# BEP31_RPM_BAR_switchedRES_2.net
KiCad netlist of a schematic drawn in EAGLE
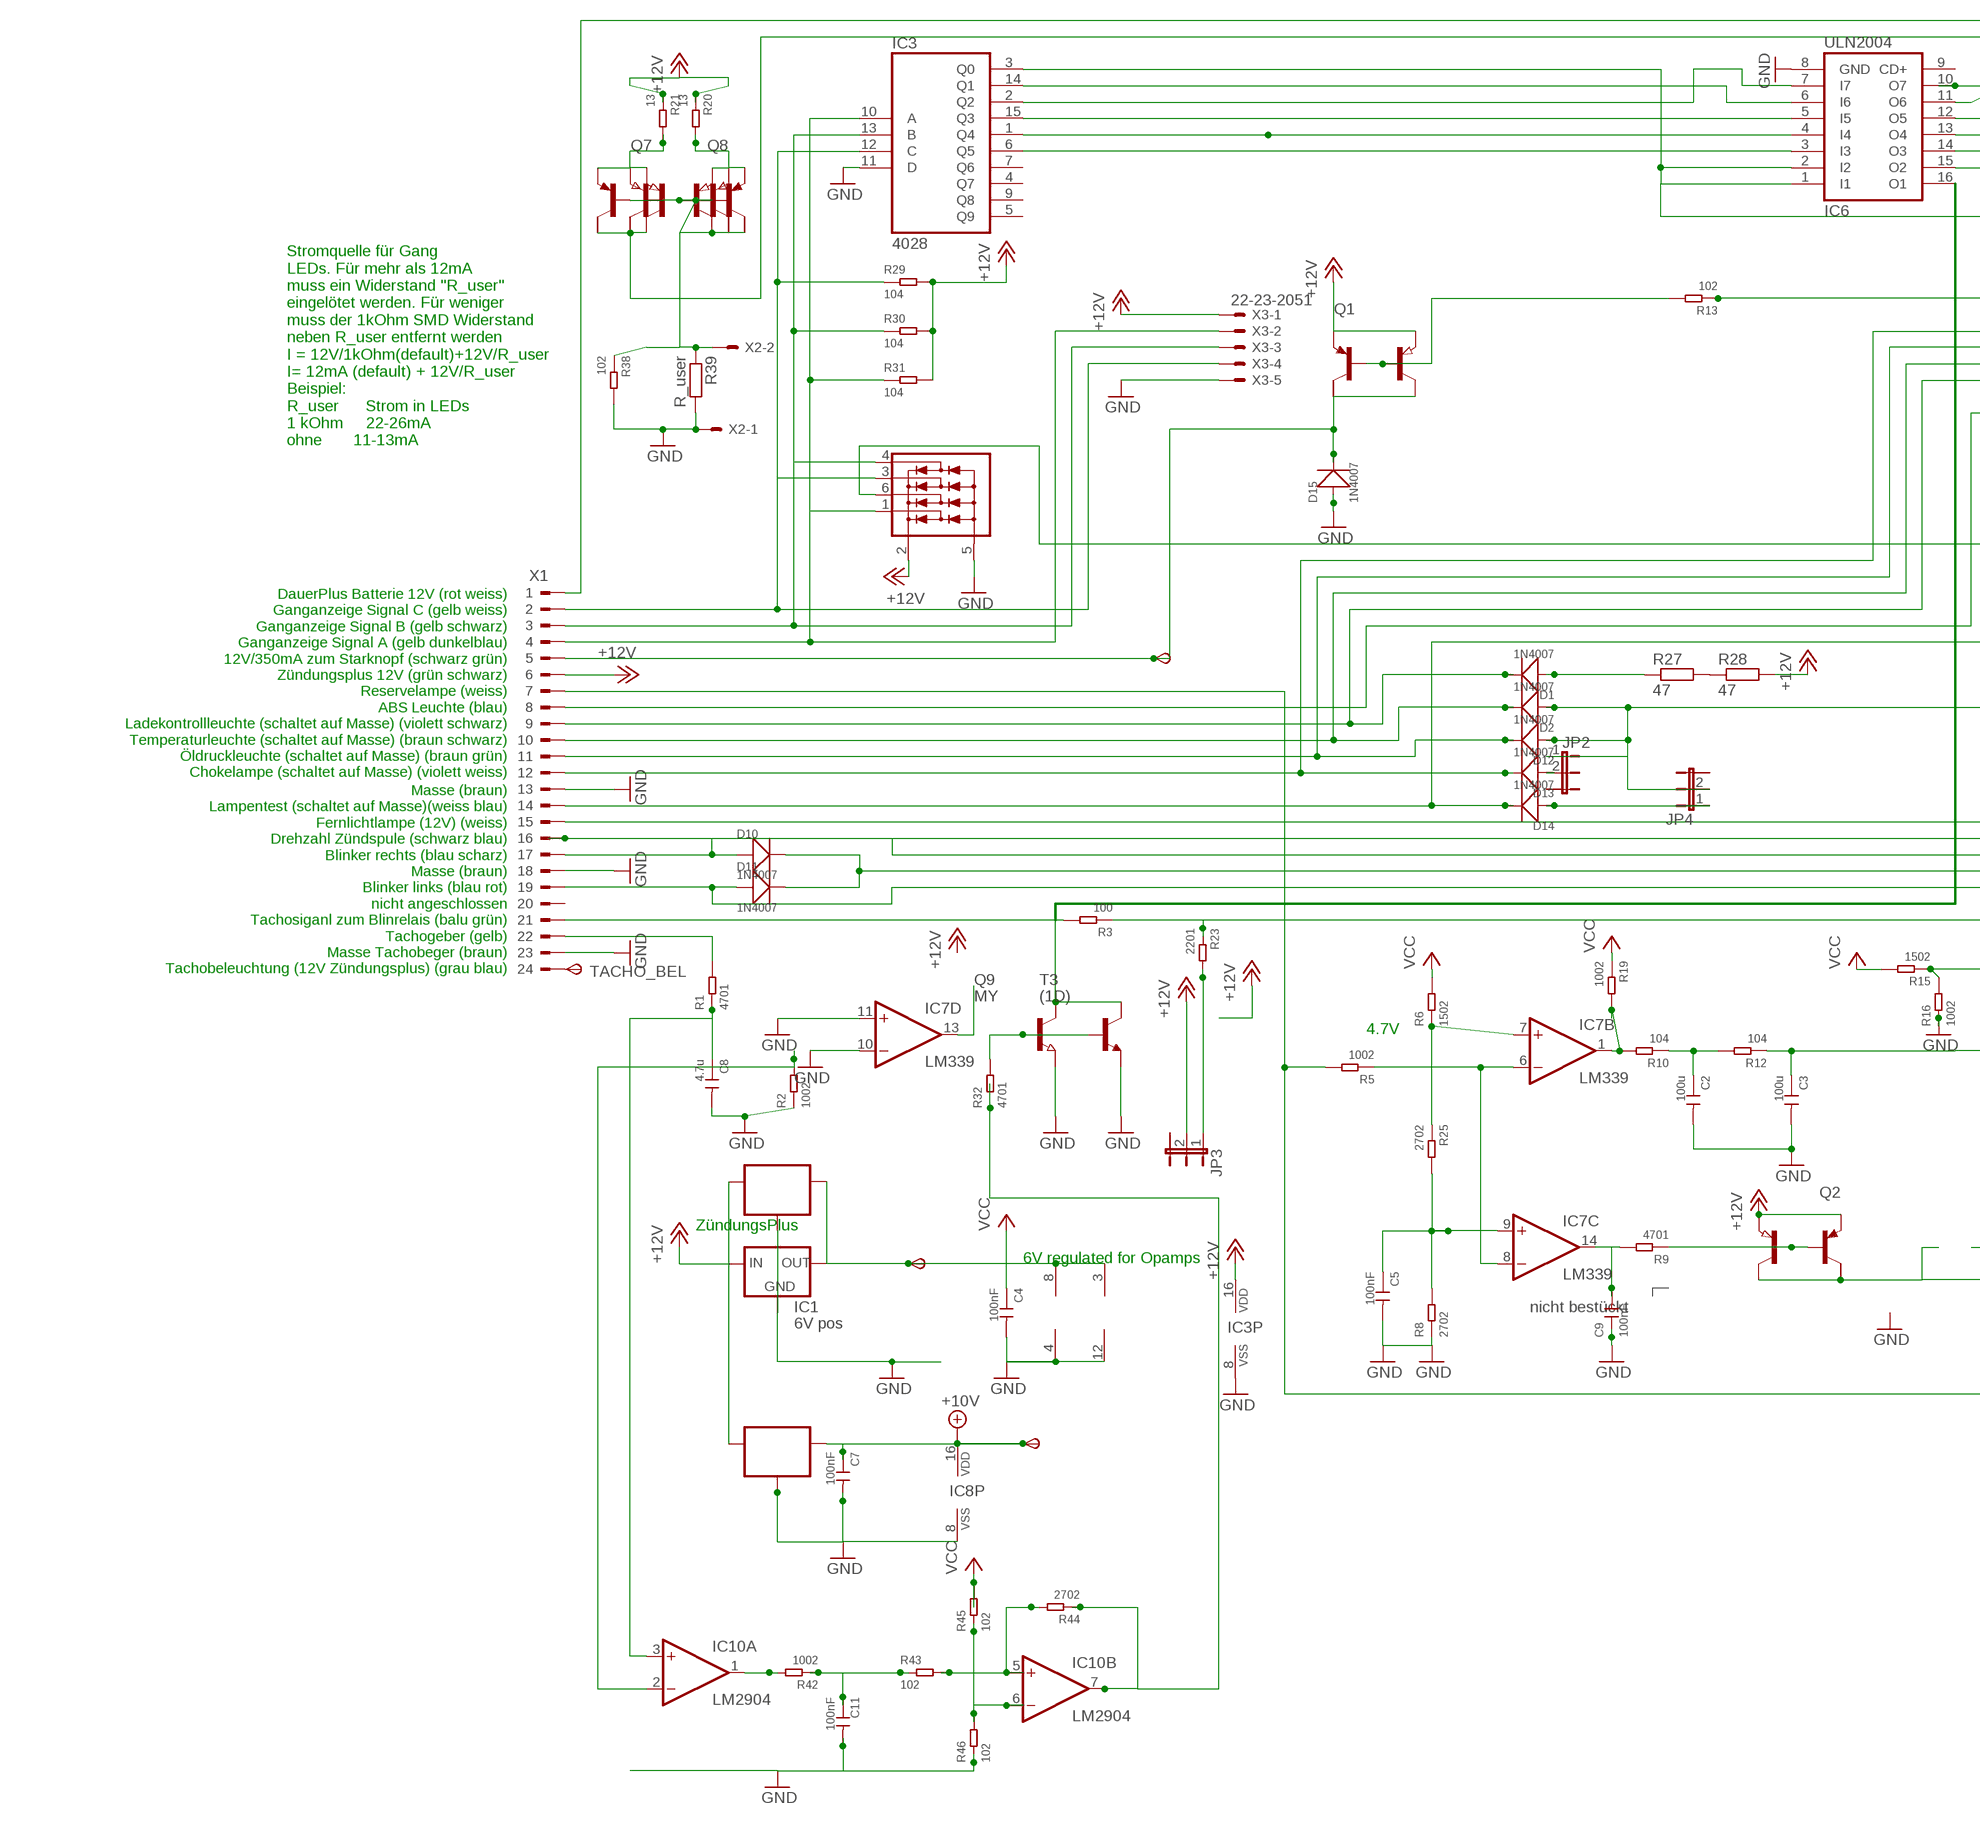
[diagram p0: schematic, sheet 1, part 1 of 2]
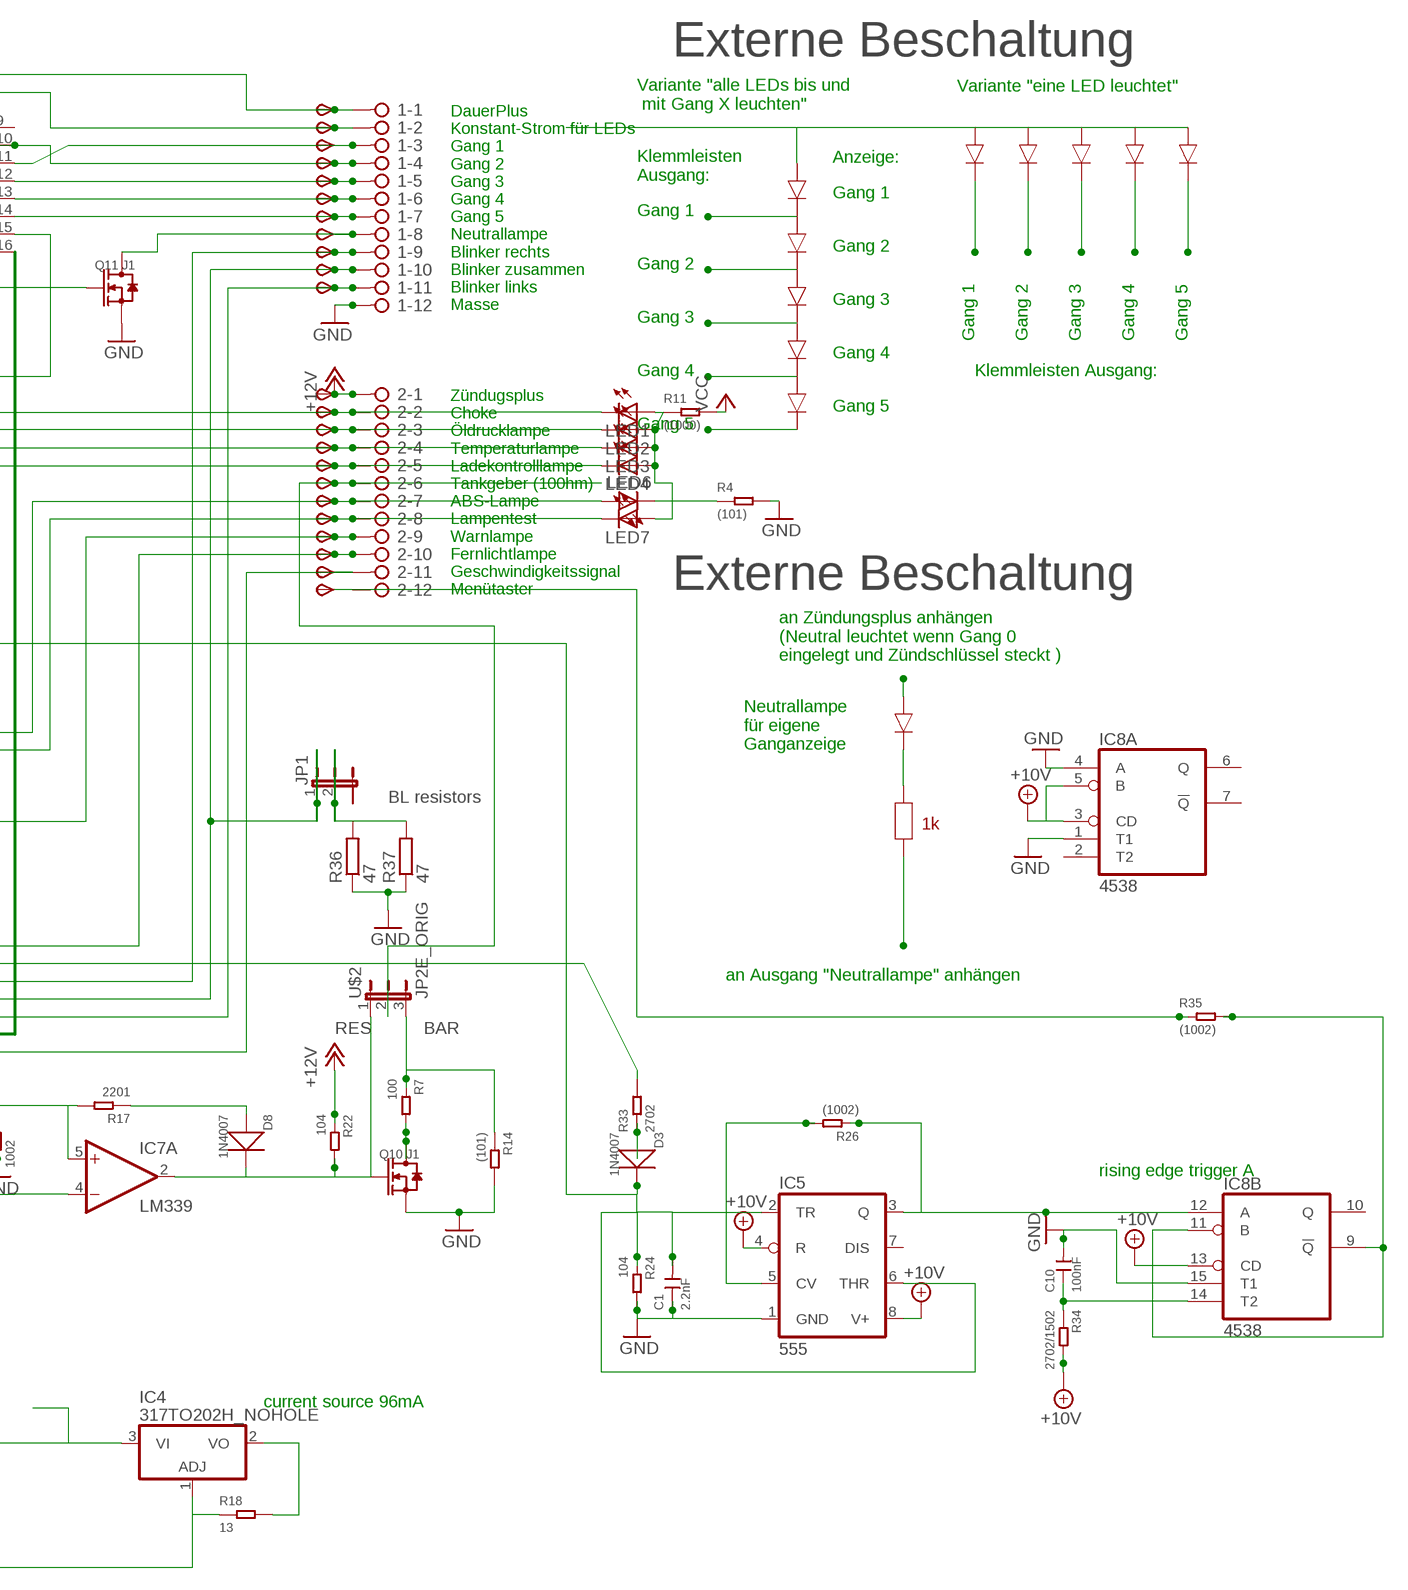
[diagram p1: schematic, sheet 1, part 2 of 2]

(export (version "E")
  (design (tool "Eeschema 10.0.6"))
  (components
    (comp (ref "1")
      (value "2081-1132")
      (footprint "eagle-import:12-PIN")
      (libsource (lib "eagle-import") (part "2081-1132"))
    )
    (comp (ref "2")
      (value "2081-1132")
      (footprint "eagle-import:12-PIN")
      (libsource (lib "eagle-import") (part "2081-1132"))
    )
    (comp (ref "6V")
      (value "TPSB2.0")
      (footprint "eagle-import:B2.0")
      (libsource (lib "eagle-import") (part "TPSB2.0"))
    )
    (comp (ref "10V")
      (value "TPSB2.0")
      (footprint "eagle-import:B2.0")
      (libsource (lib "eagle-import") (part "TPSB2.0"))
    )
    (comp (ref "C1")
      (value "2.2nF")
      (footprint "eagle-import:C0805")
      (fields (field (name "MPN") "CC0805KRX7R9BB104"))
      (libsource (lib "eagle-import") (part "CERAMIC-100NF-50V-10%-X7R(0805)"))
    )
    (comp (ref "C2")
      (value "100u")
      (footprint "eagle-import:C1206")
      (fields (field (name "MPN") "GRM31CR60J107ME39L"))
      (libsource (lib "eagle-import") (part "CERAMIC-100UF-6.3V-20%-X5R(1206)"))
    )
    (comp (ref "C3")
      (value "100u")
      (footprint "eagle-import:C1206")
      (fields (field (name "MPN") "GRM31CR60J107ME39L"))
      (libsource (lib "eagle-import") (part "CERAMIC-100UF-6.3V-20%-X5R(1206)"))
    )
    (comp (ref "C4")
      (value "100nF")
      (footprint "eagle-import:C0805")
      (fields (field (name "MPN") "CC0805KRX7R9BB104"))
      (libsource (lib "eagle-import") (part "CERAMIC-100NF-50V-10%-X7R(0805)"))
    )
    (comp (ref "C5")
      (value "100nF")
      (footprint "eagle-import:C0805")
      (fields (field (name "MPN") "CC0805KRX7R9BB104"))
      (libsource (lib "eagle-import") (part "CERAMIC-100NF-50V-10%-X7R(0805)"))
    )
    (comp (ref "C7")
      (value "100nF")
      (footprint "eagle-import:C0805")
      (fields (field (name "MPN") "CC0805KRX7R9BB104"))
      (libsource (lib "eagle-import") (part "CERAMIC-100NF-50V-10%-X7R(0805)"))
    )
    (comp (ref "C8")
      (value "4.7u")
      (footprint "eagle-import:C0805")
      (fields (field (name "MPN") "CC0805KKX5R8BB475"))
      (libsource (lib "eagle-import") (part "CERAMIC-4.7UF-25V-10%-X5R(0805)"))
    )
    (comp (ref "C9")
      (value "100nF")
      (footprint "eagle-import:C0805")
      (fields (field (name "MPN") "CC0805KRX7R9BB104"))
      (libsource (lib "eagle-import") (part "CERAMIC-100NF-50V-10%-X7R(0805)"))
    )
    (comp (ref "C10")
      (value "100nF")
      (footprint "eagle-import:C0805")
      (fields (field (name "MPN") "CC0805KRX7R9BB104"))
      (libsource (lib "eagle-import") (part "CERAMIC-100NF-50V-10%-X7R(0805)"))
    )
    (comp (ref "C11")
      (value "100nF")
      (footprint "eagle-import:C0805")
      (fields (field (name "MPN") "CC0805KRX7R9BB104"))
      (libsource (lib "eagle-import") (part "CERAMIC-100NF-50V-10%-X7R(0805)"))
    )
    (comp (ref "D1")
      (value "1N4007")
      (footprint "eagle-import:DO-214AC")
      (libsource (lib "eagle-import") (part "DIODE-GEN-PURPOSE-1KV-1A(DO-214AC)"))
    )
    (comp (ref "D2")
      (value "1N4007")
      (footprint "eagle-import:DO-214AC-1206MOUNT")
      (libsource (lib "eagle-import") (part "DIODE-GEN-PURPOSE-1KV-1A(DO-214AC)DO-214AC/1206"))
    )
    (comp (ref "D3")
      (value "1N4007")
      (footprint "eagle-import:DO-214AC")
      (libsource (lib "eagle-import") (part "DIODE-GEN-PURPOSE-1KV-1A(DO-214AC)"))
    )
    (comp (ref "D8")
      (value "1N4007")
      (footprint "eagle-import:DO-214AC")
      (libsource (lib "eagle-import") (part "DIODE-GEN-PURPOSE-1KV-1A(DO-214AC)"))
    )
    (comp (ref "D10")
      (value "1N4007")
      (footprint "eagle-import:DO-214AC")
      (libsource (lib "eagle-import") (part "DIODE-GEN-PURPOSE-1KV-1A(DO-214AC)"))
    )
    (comp (ref "D11")
      (value "1N4007")
      (footprint "eagle-import:DO-214AC")
      (libsource (lib "eagle-import") (part "DIODE-GEN-PURPOSE-1KV-1A(DO-214AC)"))
    )
    (comp (ref "D12")
      (value "1N4007")
      (footprint "eagle-import:DO-214AC-1206MOUNT")
      (libsource (lib "eagle-import") (part "DIODE-GEN-PURPOSE-1KV-1A(DO-214AC)DO-214AC/1206"))
    )
    (comp (ref "D13")
      (value "1N4007")
      (footprint "eagle-import:DO-214AC-1206MOUNT")
      (libsource (lib "eagle-import") (part "DIODE-GEN-PURPOSE-1KV-1A(DO-214AC)DO-214AC/1206"))
    )
    (comp (ref "D14")
      (value "1N4007")
      (footprint "eagle-import:DO-214AC-1206MOUNT")
      (libsource (lib "eagle-import") (part "DIODE-GEN-PURPOSE-1KV-1A(DO-214AC)DO-214AC/1206"))
    )
    (comp (ref "D15")
      (value "1N4007")
      (footprint "eagle-import:DO-214AC")
      (libsource (lib "eagle-import") (part "DIODE-GEN-PURPOSE-1KV-1A(DO-214AC)"))
    )
    (comp (ref "IC1")
      (value "6V pos")
      (footprint "eagle-import:78LXX")
      (libsource (lib "eagle-import") (part "v-reg_78LXX"))
    )
    (comp (ref "IC2")
      (value "78LXXSOT89_ROUND")
      (footprint "eagle-import:SOT89_ROUND")
      (libsource (lib "eagle-import") (part "78LXXSOT89_ROUND"))
    )
    (comp (ref "IC3")
      (value "4028")
      (footprint "eagle-import:SO16")
      (libsource (lib "eagle-import") (part "4028D"))
    )
    (comp (ref "IC4")
      (value "317TO202H_NOHOLE")
      (footprint "eagle-import:TO220H_NOHOLE")
      (libsource (lib "eagle-import") (part "317TO202H_NOHOLE"))
    )
    (comp (ref "IC5")
      (value "555")
      (footprint "eagle-import:SO08")
      (libsource (lib "eagle-import") (part "555DNE"))
    )
    (comp (ref "IC6")
      (value "ULN2004")
      (footprint "eagle-import:SO16")
      (libsource (lib "eagle-import") (part "ULN2004AD"))
    )
    (comp (ref "IC7")
      (value "LM339")
      (footprint "eagle-import:SO14")
      (libsource (lib "eagle-import") (part "LM339D"))
    )
    (comp (ref "IC8")
      (value "4538")
      (footprint "eagle-import:SO16")
      (libsource (lib "eagle-import") (part "4538D"))
    )
    (comp (ref "IC9")
      (value "78LXXSOT89_ROUND")
      (footprint "eagle-import:SOT89_ROUND")
      (libsource (lib "eagle-import") (part "78LXXSOT89_ROUND"))
    )
    (comp (ref "IC10")
      (value "LM2904")
      (footprint "eagle-import:SO08")
      (libsource (lib "eagle-import") (part "LM358D"))
    )
    (comp (ref "JP1")
      (value "JP2EJP2_SMALLPADS")
      (footprint "eagle-import:JP2_SMALLPADS")
      (libsource (lib "eagle-import") (part "JP2EJP2_SMALLPADS"))
    )
    (comp (ref "JP2")
      (value "JP2EJP2_SMALLPADS")
      (footprint "eagle-import:JP2_SMALLPADS")
      (libsource (lib "eagle-import") (part "JP2EJP2_SMALLPADS"))
    )
    (comp (ref "JP3")
      (value "JP2EJP2_SMALLPADS")
      (footprint "eagle-import:JP2_SMALLPADS")
      (libsource (lib "eagle-import") (part "JP2EJP2_SMALLPADS"))
    )
    (comp (ref "JP4")
      (value "JP2EJP2_SMALLPADS")
      (footprint "eagle-import:JP2_SMALLPADS")
      (libsource (lib "eagle-import") (part "JP2EJP2_SMALLPADS"))
    )
    (comp (ref "LED1")
      (value "LEDLD260")
      (footprint "eagle-import:LD260")
      (libsource (lib "eagle-import") (part "LEDLD260"))
    )
    (comp (ref "LED2")
      (value "LEDLD260")
      (footprint "eagle-import:LD260")
      (libsource (lib "eagle-import") (part "LEDLD260"))
    )
    (comp (ref "LED3")
      (value "LEDLD260")
      (footprint "eagle-import:LD260")
      (libsource (lib "eagle-import") (part "LEDLD260"))
    )
    (comp (ref "LED4")
      (value "LEDLD260")
      (footprint "eagle-import:LD260")
      (libsource (lib "eagle-import") (part "LEDLD260"))
    )
    (comp (ref "LED6")
      (value "LEDLD260")
      (footprint "eagle-import:LD260")
      (libsource (lib "eagle-import") (part "LEDLD260"))
    )
    (comp (ref "LED7")
      (value "LEDLD260")
      (footprint "eagle-import:LD260")
      (libsource (lib "eagle-import") (part "LEDLD260"))
    )
    (comp (ref "Q1")
      (value "PNP-TRANSISTOR_SOT89")
      (footprint "eagle-import:SOT89")
      (libsource (lib "eagle-import") (part "PNP-TRANSISTOR_SOT89"))
    )
    (comp (ref "Q2")
      (value "PNP-TRANSISTOR_SOT89")
      (footprint "eagle-import:SOT89")
      (libsource (lib "eagle-import") (part "PNP-TRANSISTOR_SOT89"))
    )
    (comp (ref "Q3")
      (value "AH-16")
      (footprint "eagle-import:SOT223")
      (libsource (lib "eagle-import") (part "BCP53T1"))
    )
    (comp (ref "Q4")
      (value "(AH-16)")
      (footprint "eagle-import:SOT223")
      (libsource (lib "eagle-import") (part "BCP53T1"))
    )
    (comp (ref "Q5")
      (value "(AH-16)")
      (footprint "eagle-import:SOT223")
      (libsource (lib "eagle-import") (part "BCP53T1"))
    )
    (comp (ref "Q6")
      (value "(AH-16)")
      (footprint "eagle-import:SOT223")
      (libsource (lib "eagle-import") (part "BCP53T1"))
    )
    (comp (ref "Q7")
      (value "PNP-TRANSISTOR_SOT89")
      (footprint "eagle-import:SOT89")
      (libsource (lib "eagle-import") (part "PNP-TRANSISTOR_SOT89"))
    )
    (comp (ref "Q8")
      (value "PNP-TRANSISTOR_SOT89")
      (footprint "eagle-import:SOT89")
      (libsource (lib "eagle-import") (part "PNP-TRANSISTOR_SOT89"))
    )
    (comp (ref "Q9")
      (value "MY")
      (footprint "eagle-import:SOT89")
      (libsource (lib "eagle-import") (part "NPN-TRANSISTOR_SOT89"))
    )
    (comp (ref "Q10")
      (value "J1")
      (footprint "eagle-import:SOT-23")
      (fields (field (name "MPN") "BSS138W-7-F"))
      (libsource (lib "eagle-import") (part "SMD-MOSFET-N-CH-50V-200MA-BSS138W-7-F(SOT-23)"))
    )
    (comp (ref "Q11")
      (value "J1")
      (footprint "eagle-import:SOT-23")
      (fields (field (name "MPN") "BSS138W-7-F"))
      (libsource (lib "eagle-import") (part "SMD-MOSFET-N-CH-50V-200MA-BSS138W-7-F(SOT-23)"))
    )
    (comp (ref "R1")
      (value "4701")
      (footprint "eagle-import:R0805")
      (fields (field (name "MPN") "RC0805JR-074K7L"))
      (libsource (lib "eagle-import") (part "SMD-RES-4.7K-5%-1/8W(0805)"))
    )
    (comp (ref "R2")
      (value "1002")
      (footprint "eagle-import:R0805")
      (fields (field (name "MPN") "RC0805FR-0710KL"))
      (libsource (lib "eagle-import") (part "SMD-RES-10K-1%-1/8W(0805)"))
    )
    (comp (ref "R3")
      (value "100")
      (footprint "eagle-import:R0805")
      (fields (field (name "MPN") "RC0805JR-07220RL"))
      (libsource (lib "eagle-import") (part "SMD-RES-220R-5%-1/8W(0805)"))
    )
    (comp (ref "R4")
      (value "(101)")
      (footprint "eagle-import:R0805")
      (fields (field (name "MPN") "RC0805JR-07100RL"))
      (libsource (lib "eagle-import") (part "SMD-RES-100R-5%-1/8W(0805)"))
    )
    (comp (ref "R5")
      (value "1002")
      (footprint "eagle-import:R0805")
      (fields (field (name "MPN") "RC0805FR-0710KL"))
      (libsource (lib "eagle-import") (part "SMD-RES-10K-1%-1/8W(0805)"))
    )
    (comp (ref "R6")
      (value "1502")
      (footprint "eagle-import:R0805")
      (fields (field (name "MPN") "RC0805FR-0710KL"))
      (libsource (lib "eagle-import") (part "SMD-RES-10K-1%-1/8W(0805)"))
    )
    (comp (ref "R7")
      (value "100")
      (footprint "eagle-import:R0805")
      (fields (field (name "MPN") "RC0805JR-072K2L"))
      (libsource (lib "eagle-import") (part "SMD-RES-2.2K-5%-1/8W(0805)"))
    )
    (comp (ref "R8")
      (value "2702")
      (footprint "eagle-import:R0805")
      (fields (field (name "MPN") "RC0805JR-074K7L"))
      (libsource (lib "eagle-import") (part "SMD-RES-4.7K-5%-1/8W(0805)"))
    )
    (comp (ref "R9")
      (value "4701")
      (footprint "eagle-import:R0805")
      (fields (field (name "MPN") "RC0805JR-074K7L"))
      (libsource (lib "eagle-import") (part "SMD-RES-4.7K-5%-1/8W(0805)"))
    )
    (comp (ref "R10")
      (value "104")
      (footprint "eagle-import:R0805")
      (fields (field (name "MPN") "RC0805FR-0710KL"))
      (libsource (lib "eagle-import") (part "SMD-RES-10K-1%-1/8W(0805)"))
    )
    (comp (ref "R11")
      (value "(1000)")
      (footprint "eagle-import:R0805")
      (fields (field (name "MPN") "RC0805JR-07100RL"))
      (libsource (lib "eagle-import") (part "SMD-RES-100R-5%-1/8W(0805)"))
    )
    (comp (ref "R12")
      (value "104")
      (footprint "eagle-import:R0805")
      (fields (field (name "MPN") "RC0805FR-0710KL"))
      (libsource (lib "eagle-import") (part "SMD-RES-10K-1%-1/8W(0805)"))
    )
    (comp (ref "R13")
      (value "102")
      (footprint "eagle-import:R0805")
      (fields (field (name "MPN") "RC0805JR-071KL"))
      (libsource (lib "eagle-import") (part "SMD-RES-1K-5%-1/8W(0805)"))
    )
    (comp (ref "R14")
      (value "(101)")
      (footprint "eagle-import:R0805")
      (fields (field (name "MPN") "RC0805JR-072K2L"))
      (libsource (lib "eagle-import") (part "SMD-RES-2.2K-5%-1/8W(0805)"))
    )
    (comp (ref "R15")
      (value "1502")
      (footprint "eagle-import:R0805")
      (fields (field (name "MPN") "RC0805FR-0710KL"))
      (libsource (lib "eagle-import") (part "SMD-RES-10K-1%-1/8W(0805)"))
    )
    (comp (ref "R16")
      (value "1002")
      (footprint "eagle-import:R0805")
      (fields (field (name "MPN") "RC0805FR-0710KL"))
      (libsource (lib "eagle-import") (part "SMD-RES-10K-1%-1/8W(0805)"))
    )
    (comp (ref "R17")
      (value "2201")
      (footprint "eagle-import:R0805")
      (fields (field (name "MPN") "RC0805JR-072K2L"))
      (libsource (lib "eagle-import") (part "SMD-RES-2.2K-5%-1/8W(0805)"))
    )
    (comp (ref "R18")
      (value "13")
      (footprint "eagle-import:R1206")
      (fields (field (name "MPN") "RC1206JR-0713RL"))
      (libsource (lib "eagle-import") (part "SMD-RES-13R-5%-1/4W(1206)"))
    )
    (comp (ref "R19")
      (value "1002")
      (footprint "eagle-import:R0805")
      (fields (field (name "MPN") "RC0805FR-0710KL"))
      (libsource (lib "eagle-import") (part "SMD-RES-10K-1%-1/8W(0805)"))
    )
    (comp (ref "R20")
      (value "13")
      (footprint "eagle-import:R1206")
      (fields (field (name "MPN") "RC1206JR-0713RL"))
      (libsource (lib "eagle-import") (part "SMD-RES-13R-5%-1/4W(1206)"))
    )
    (comp (ref "R21")
      (value "13")
      (footprint "eagle-import:R1206")
      (fields (field (name "MPN") "RC1206JR-0713RL"))
      (libsource (lib "eagle-import") (part "SMD-RES-13R-5%-1/4W(1206)"))
    )
    (comp (ref "R22")
      (value "104")
      (footprint "eagle-import:R0805")
      (fields (field (name "MPN") "RC0805FR-0710KL"))
      (libsource (lib "eagle-import") (part "SMD-RES-10K-1%-1/8W(0805)"))
    )
    (comp (ref "R23")
      (value "2201")
      (footprint "eagle-import:R0805")
      (fields (field (name "MPN") "RC0805JR-072K2L"))
      (libsource (lib "eagle-import") (part "SMD-RES-2.2K-5%-1/8W(0805)"))
    )
    (comp (ref "R24")
      (value "104")
      (footprint "eagle-import:R0805")
      (fields (field (name "MPN") "RC0805FR-0710KL"))
      (libsource (lib "eagle-import") (part "SMD-RES-10K-1%-1/8W(0805)"))
    )
    (comp (ref "R25")
      (value "2702")
      (footprint "eagle-import:R0805")
      (fields (field (name "MPN") "RC0805JR-074K7L"))
      (libsource (lib "eagle-import") (part "SMD-RES-4.7K-5%-1/8W(0805)"))
    )
    (comp (ref "R26")
      (value "(1002)")
      (footprint "eagle-import:R0805")
      (fields (field (name "MPN") "RC0805FR-0710KL"))
      (libsource (lib "eagle-import") (part "SMD-RES-10K-1%-1/8W(0805)"))
    )
    (comp (ref "R27")
      (value "47")
      (footprint "eagle-import:V235_17_1MM")
      (libsource (lib "eagle-import") (part "R-EU_V235/17_1MM"))
    )
    (comp (ref "R28")
      (value "47")
      (footprint "eagle-import:V235_17_1MM")
      (libsource (lib "eagle-import") (part "R-EU_V235/17_1MM"))
    )
    (comp (ref "R29")
      (value "104")
      (footprint "eagle-import:R0805")
      (fields (field (name "MPN") "RC0805FR-0710KL"))
      (libsource (lib "eagle-import") (part "SMD-RES-10K-1%-1/8W(0805)"))
    )
    (comp (ref "R30")
      (value "104")
      (footprint "eagle-import:R0805")
      (fields (field (name "MPN") "RC0805FR-0710KL"))
      (libsource (lib "eagle-import") (part "SMD-RES-10K-1%-1/8W(0805)"))
    )
    (comp (ref "R31")
      (value "104")
      (footprint "eagle-import:R0805")
      (fields (field (name "MPN") "RC0805FR-0710KL"))
      (libsource (lib "eagle-import") (part "SMD-RES-10K-1%-1/8W(0805)"))
    )
    (comp (ref "R32")
      (value "4701")
      (footprint "eagle-import:R0805")
      (fields (field (name "MPN") "RC0805JR-074K7L"))
      (libsource (lib "eagle-import") (part "SMD-RES-4.7K-5%-1/8W(0805)"))
    )
    (comp (ref "R33")
      (value "2702")
      (footprint "eagle-import:R0805")
      (fields (field (name "MPN") "RC0805FR-0710KL"))
      (libsource (lib "eagle-import") (part "SMD-RES-10K-1%-1/8W(0805)"))
    )
    (comp (ref "R34")
      (value "2702/1502")
      (footprint "eagle-import:R0805")
      (fields (field (name "MPN") "RC0805JR-074K7L"))
      (libsource (lib "eagle-import") (part "SMD-RES-4.7K-5%-1/8W(0805)"))
    )
    (comp (ref "R35")
      (value "(1002)")
      (footprint "eagle-import:R0805")
      (fields (field (name "MPN") "RC0805JR-074K7L"))
      (libsource (lib "eagle-import") (part "SMD-RES-4.7K-5%-1/8W(0805)"))
    )
    (comp (ref "R36")
      (value "47")
      (footprint "eagle-import:V235_17_1MM")
      (libsource (lib "eagle-import") (part "R-EU_V235/17_1MM"))
    )
    (comp (ref "R37")
      (value "47")
      (footprint "eagle-import:V235_17_1MM")
      (libsource (lib "eagle-import") (part "R-EU_V235/17_1MM"))
    )
    (comp (ref "R38")
      (value "102")
      (footprint "eagle-import:R0805")
      (fields (field (name "MPN") "RC0805JR-071KL"))
      (libsource (lib "eagle-import") (part "SMD-RES-1K-5%-1/8W(0805)"))
    )
    (comp (ref "R39")
      (value "R_user")
      (footprint "eagle-import:R0805")
      (libsource (lib "eagle-import") (part "R-EU_R0805"))
    )
    (comp (ref "R42")
      (value "1002")
      (footprint "eagle-import:R0805")
      (fields (field (name "MPN") "RC0805FR-0710KL"))
      (libsource (lib "eagle-import") (part "SMD-RES-10K-1%-1/8W(0805)"))
    )
    (comp (ref "R43")
      (value "102")
      (footprint "eagle-import:R0805")
      (fields (field (name "MPN") "RC0805JR-071KL"))
      (libsource (lib "eagle-import") (part "SMD-RES-1K-5%-1/8W(0805)"))
    )
    (comp (ref "R44")
      (value "2702")
      (footprint "eagle-import:R0805")
      (fields (field (name "MPN") "RC0805JR-074K7L"))
      (libsource (lib "eagle-import") (part "SMD-RES-4.7K-5%-1/8W(0805)"))
    )
    (comp (ref "R45")
      (value "102")
      (footprint "eagle-import:R0805")
      (fields (field (name "MPN") "RC0805JR-071KL"))
      (libsource (lib "eagle-import") (part "SMD-RES-1K-5%-1/8W(0805)"))
    )
    (comp (ref "R46")
      (value "102")
      (footprint "eagle-import:R0805")
      (fields (field (name "MPN") "RC0805JR-071KL"))
      (libsource (lib "eagle-import") (part "SMD-RES-1K-5%-1/8W(0805)"))
    )
    (comp (ref "START")
      (value "TPSB2.0")
      (footprint "eagle-import:B2.0")
      (libsource (lib "eagle-import") (part "TPSB2.0"))
    )
    (comp (ref "T1")
      (value "PNP2SM8")
      (footprint "eagle-import:SM8")
      (libsource (lib "eagle-import") (part "PNP2SM8"))
    )
    (comp (ref "T3")
      (value "(1D)")
      (footprint "eagle-import:SOT23-BEC")
      (libsource (lib "eagle-import") (part "-NPN-SOT23-BECMMBTA42LT1"))
    )
    (comp (ref "TACHO_BEL")
      (value "TPSP1_1MM")
      (footprint "eagle-import:P1_1.0MM")
      (libsource (lib "eagle-import") (part "TPSP1_1MM"))
    )
    (comp (ref "TP1")
      (value "TPSB2.0")
      (footprint "eagle-import:B2.0")
      (libsource (lib "eagle-import") (part "TPSB2.0"))
    )
    (comp (ref "TP2")
      (value "TPSB2.0")
      (footprint "eagle-import:B2.0")
      (libsource (lib "eagle-import") (part "TPSB2.0"))
    )
    (comp (ref "TP3")
      (value "TPSB2.0")
      (footprint "eagle-import:B2.0")
      (libsource (lib "eagle-import") (part "TPSB2.0"))
    )
    (comp (ref "TP4")
      (value "TPSB2.0")
      (footprint "eagle-import:B2.0")
      (libsource (lib "eagle-import") (part "TPSB2.0"))
    )
    (comp (ref "TP5")
      (value "TPSB2.0")
      (footprint "eagle-import:B2.0")
      (libsource (lib "eagle-import") (part "TPSB2.0"))
    )
    (comp (ref "TP6")
      (value "TPSB2.0")
      (footprint "eagle-import:B2.0")
      (libsource (lib "eagle-import") (part "TPSB2.0"))
    )
    (comp (ref "TP7")
      (value "TPSB2.0")
      (footprint "eagle-import:B2.0")
      (libsource (lib "eagle-import") (part "TPSB2.0"))
    )
    (comp (ref "TP8")
      (value "TPSB2.0")
      (footprint "eagle-import:B2.0")
      (libsource (lib "eagle-import") (part "TPSB2.0"))
    )
    (comp (ref "TP9")
      (value "TPSB2.0")
      (footprint "eagle-import:B2.0")
      (libsource (lib "eagle-import") (part "TPSB2.0"))
    )
    (comp (ref "TP10")
      (value "TPSB2.0")
      (footprint "eagle-import:B2.0")
      (libsource (lib "eagle-import") (part "TPSB2.0"))
    )
    (comp (ref "TP11")
      (value "TPSB2.0")
      (footprint "eagle-import:B2.0")
      (libsource (lib "eagle-import") (part "TPSB2.0"))
    )
    (comp (ref "TP12")
      (value "TPSB2.0")
      (footprint "eagle-import:B2.0")
      (libsource (lib "eagle-import") (part "TPSB2.0"))
    )
    (comp (ref "TP13")
      (value "TPSB2.0")
      (footprint "eagle-import:B2.0")
      (libsource (lib "eagle-import") (part "TPSB2.0"))
    )
    (comp (ref "TP16")
      (value "TPSB2.0")
      (footprint "eagle-import:B2.0")
      (libsource (lib "eagle-import") (part "TPSB2.0"))
    )
    (comp (ref "TP17")
      (value "TPSB2.0")
      (footprint "eagle-import:B2.0")
      (libsource (lib "eagle-import") (part "TPSB2.0"))
    )
    (comp (ref "TP18")
      (value "TPSB2.0")
      (footprint "eagle-import:B2.0")
      (libsource (lib "eagle-import") (part "TPSB2.0"))
    )
    (comp (ref "TP19")
      (value "TPSB2.0")
      (footprint "eagle-import:B2.0")
      (libsource (lib "eagle-import") (part "TPSB2.0"))
    )
    (comp (ref "TP21")
      (value "TPSB2.0")
      (footprint "eagle-import:B2.0")
      (libsource (lib "eagle-import") (part "TPSB2.0"))
    )
    (comp (ref "TP22")
      (value "TPSB2.0")
      (footprint "eagle-import:B2.0")
      (libsource (lib "eagle-import") (part "TPSB2.0"))
    )
    (comp (ref "TP23")
      (value "TPSB2.0")
      (footprint "eagle-import:B2.0")
      (libsource (lib "eagle-import") (part "TPSB2.0"))
    )
    (comp (ref "TP24")
      (value "TPSB1,27")
      (footprint "eagle-import:B1,27")
      (libsource (lib "eagle-import") (part "TPSB1,27"))
    )
    (comp (ref "TP25")
      (value "TPSB2.0")
      (footprint "eagle-import:B2.0")
      (libsource (lib "eagle-import") (part "TPSB2.0"))
    )
    (comp (ref "TP26")
      (value "TPSB2.0")
      (footprint "eagle-import:B2.0")
      (libsource (lib "eagle-import") (part "TPSB2.0"))
    )
    (comp (ref "U$2")
      (value "JP2E_ORIG")
      (footprint "eagle-import:JP2_ORIG_SMALLPADS")
      (libsource (lib "eagle-import") (part "JP2E_ORIG"))
    )
    (comp (ref "U$3")
      (value "NUP4304SOT457_R")
      (footprint "eagle-import:SOT457R_PHILIPS")
      (libsource (lib "eagle-import") (part "NUP4304SOT457_R"))
    )
    (comp (ref "X1")
      (value "CON_BMWV2")
      (footprint "eagle-import:24-PIN_V2")
      (libsource (lib "eagle-import") (part "CON_BMWV2"))
    )
    (comp (ref "X2")
      (value "22-23-2021")
      (footprint "eagle-import:22-23-2021")
      (fields (field (name "MF") "MOLEX"))
      (libsource (lib "eagle-import") (part "22-23-2021"))
    )
    (comp (ref "X3")
      (value "22-23-2051")
      (footprint "eagle-import:22-23-2051")
      (fields (field (name "MF") "MOLEX"))
      (libsource (lib "eagle-import") (part "22-23-2051"))
    )
  )
  (nets
    (net (code "1") (name "+10V") (class "Default")
      (node (ref "10V") (pin "TP") (pinfunction "PP_TP") (pintype "input"))
      (node (ref "C7") (pin "1") (pinfunction "1_1") (pintype "passive"))
      (node (ref "IC5") (pin "4") (pinfunction "R_4") (pintype "input"))
      (node (ref "IC5") (pin "8") (pinfunction "V+_8") (pintype "power_in"))
      (node (ref "IC8") (pin "13") (pinfunction "CD_13") (pintype "input"))
      (node (ref "IC8") (pin "16") (pinfunction "VDD_16") (pintype "power_in"))
      (node (ref "IC8") (pin "3") (pinfunction "CD_3") (pintype "input"))
      (node (ref "IC8") (pin "5") (pinfunction "B_5") (pintype "input"))
      (node (ref "IC9") (pin "1") (pinfunction "OUT_1") (pintype "passive"))
      (node (ref "R34") (pin "2") (pinfunction "2_2") (pintype "passive"))
    )
    (net (code "2") (name "+12V") (class "Default")
      (node (ref "2") (pin "1") (pinfunction "KL_1") (pintype "passive"))
      (node (ref "IC1") (pin "IN") (pinfunction "IN_IN") (pintype "input"))
      (node (ref "IC2") (pin "3") (pinfunction "IN_3") (pintype "input"))
      (node (ref "IC3") (pin "16") (pinfunction "VDD_16") (pintype "power_in"))
      (node (ref "IC9") (pin "3") (pinfunction "IN_3") (pintype "input"))
      (node (ref "JP3") (pin "2") (pinfunction "2_2") (pintype "passive"))
      (node (ref "Q1") (pin "3") (pinfunction "E_3") (pintype "passive"))
      (node (ref "Q2") (pin "3") (pinfunction "E_3") (pintype "passive"))
      (node (ref "Q3") (pin "3") (pinfunction "E_3") (pintype "passive"))
      (node (ref "Q4") (pin "3") (pinfunction "E_3") (pintype "passive"))
      (node (ref "R20") (pin "1") (pinfunction "1_1") (pintype "passive"))
      (node (ref "R21") (pin "1") (pinfunction "1_1") (pintype "passive"))
      (node (ref "R22") (pin "1") (pinfunction "1_1") (pintype "passive"))
      (node (ref "R28") (pin "2") (pinfunction "2_2") (pintype "passive"))
      (node (ref "R29") (pin "2") (pinfunction "2_2") (pintype "passive"))
      (node (ref "R30") (pin "2") (pinfunction "2_2") (pintype "passive"))
      (node (ref "R31") (pin "2") (pinfunction "2_2") (pintype "passive"))
      (node (ref "TP12") (pin "TP") (pinfunction "PP_TP") (pintype "input"))
      (node (ref "U$3") (pin "2") (pinfunction "V+_2") (pintype "passive"))
      (node (ref "X1") (pin "6") (pinfunction "6_6") (pintype "passive"))
      (node (ref "X3") (pin "1") (pinfunction "S_1") (pintype "passive"))
    )
    (net (code "3") (name "GND") (class "Default")
      (node (ref "1") (pin "12") (pinfunction "KL_12") (pintype "passive"))
      (node (ref "C1") (pin "1") (pinfunction "1_1") (pintype "passive"))
      (node (ref "C10") (pin "2") (pinfunction "2_2") (pintype "passive"))
      (node (ref "C11") (pin "2") (pinfunction "2_2") (pintype "passive"))
      (node (ref "C2") (pin "2") (pinfunction "2_2") (pintype "passive"))
      (node (ref "C3") (pin "2") (pinfunction "2_2") (pintype "passive"))
      (node (ref "C4") (pin "2") (pinfunction "2_2") (pintype "passive"))
      (node (ref "C5") (pin "2") (pinfunction "2_2") (pintype "passive"))
      (node (ref "C7") (pin "2") (pinfunction "2_2") (pintype "passive"))
      (node (ref "C8") (pin "2") (pinfunction "2_2") (pintype "passive"))
      (node (ref "C9") (pin "1") (pinfunction "1_1") (pintype "passive"))
      (node (ref "D15") (pin "1") (pinfunction "+_1") (pintype "passive"))
      (node (ref "IC1") (pin "GND") (pinfunction "GND_GND") (pintype "input"))
      (node (ref "IC10") (pin "4") (pinfunction "V-_4") (pintype "power_in"))
      (node (ref "IC2") (pin "2") (pinfunction "GND_2") (pintype "input"))
      (node (ref "IC2") (pin "2@1") (pinfunction "GND_2@1") (pintype "input"))
      (node (ref "IC3") (pin "11") (pinfunction "D_11") (pintype "input"))
      (node (ref "IC3") (pin "8") (pinfunction "VSS_8") (pintype "power_in"))
      (node (ref "IC5") (pin "1") (pinfunction "GND_1") (pintype "power_in"))
      (node (ref "IC6") (pin "8") (pinfunction "GND_8") (pintype "power_in"))
      (node (ref "IC7") (pin "10") (pinfunction "-IN_10") (pintype "input"))
      (node (ref "IC7") (pin "11") (pinfunction "+IN_11") (pintype "input"))
      (node (ref "IC7") (pin "12") (pinfunction "GND_12") (pintype "power_in"))
      (node (ref "IC8") (pin "1") (pinfunction "T1_1") (pintype "input"))
      (node (ref "IC8") (pin "15") (pinfunction "T1_15") (pintype "input"))
      (node (ref "IC8") (pin "4") (pinfunction "A_4") (pintype "input"))
      (node (ref "IC8") (pin "8") (pinfunction "VSS_8") (pintype "power_in"))
      (node (ref "IC9") (pin "2") (pinfunction "GND_2") (pintype "input"))
      (node (ref "IC9") (pin "2@1") (pinfunction "GND_2@1") (pintype "input"))
      (node (ref "Q10") (pin "2") (pinfunction "S_2") (pintype "passive"))
      (node (ref "Q11") (pin "2") (pinfunction "S_2") (pintype "passive"))
      (node (ref "Q9") (pin "3") (pinfunction "E_3") (pintype "passive"))
      (node (ref "R14") (pin "2") (pinfunction "2_2") (pintype "passive"))
      (node (ref "R16") (pin "1") (pinfunction "1_1") (pintype "passive"))
      (node (ref "R2") (pin "1") (pinfunction "1_1") (pintype "passive"))
      (node (ref "R24") (pin "2") (pinfunction "2_2") (pintype "passive"))
      (node (ref "R36") (pin "1") (pinfunction "1_1") (pintype "passive"))
      (node (ref "R37") (pin "1") (pinfunction "1_1") (pintype "passive"))
      (node (ref "R38") (pin "2") (pinfunction "2_2") (pintype "passive"))
      (node (ref "R39") (pin "2") (pinfunction "2_2") (pintype "passive"))
      (node (ref "R4") (pin "2") (pinfunction "2_2") (pintype "passive"))
      (node (ref "R46") (pin "1") (pinfunction "1_1") (pintype "passive"))
      (node (ref "R8") (pin "1") (pinfunction "1_1") (pintype "passive"))
      (node (ref "T3") (pin "E") (pinfunction "E_E") (pintype "passive"))
      (node (ref "U$3") (pin "5") (pinfunction "V-_5") (pintype "passive"))
      (node (ref "X1") (pin "13") (pinfunction "13_13") (pintype "passive"))
      (node (ref "X1") (pin "18") (pinfunction "18_18") (pintype "passive"))
      (node (ref "X1") (pin "23") (pinfunction "23_23") (pintype "passive"))
      (node (ref "X2") (pin "1") (pinfunction "S_1") (pintype "passive"))
      (node (ref "X3") (pin "5") (pinfunction "S_5") (pintype "passive"))
    )
    (net (code "4") (name "Net-(1A-KL)") (class "Default")
      (node (ref "1") (pin "1") (pinfunction "KL_1") (pintype "passive"))
      (node (ref "TP1") (pin "TP") (pinfunction "PP_TP") (pintype "input"))
      (node (ref "X1") (pin "1") (pinfunction "1_1") (pintype "passive"))
    )
    (net (code "5") (name "Net-(1B-KL)") (class "Default")
      (node (ref "1") (pin "10") (pinfunction "KL_10") (pintype "passive"))
      (node (ref "D10") (pin "2") (pinfunction "-_2") (pintype "passive"))
      (node (ref "D11") (pin "2") (pinfunction "-_2") (pintype "passive"))
      (node (ref "JP1") (pin "1") (pinfunction "1_1") (pintype "passive"))
      (node (ref "TP10") (pin "TP") (pinfunction "PP_TP") (pintype "input"))
    )
    (net (code "6") (name "Net-(1C-KL)") (class "Default")
      (node (ref "1") (pin "11") (pinfunction "KL_11") (pintype "passive"))
      (node (ref "D11") (pin "1") (pinfunction "+_1") (pintype "passive"))
      (node (ref "TP11") (pin "TP") (pinfunction "PP_TP") (pintype "input"))
      (node (ref "X1") (pin "19") (pinfunction "19_19") (pintype "passive"))
    )
    (net (code "7") (name "Net-(1E-KL)") (class "Default")
      (node (ref "1") (pin "2") (pinfunction "KL_2") (pintype "passive"))
      (node (ref "Q5") (pin "2") (pinfunction "C_2") (pintype "passive"))
      (node (ref "Q8") (pin "2") (pinfunction "C_2") (pintype "passive"))
      (node (ref "T1") (pin "8") (pinfunction "C1_8") (pintype "passive"))
      (node (ref "TP2") (pin "TP") (pinfunction "PP_TP") (pintype "input"))
    )
    (net (code "8") (name "Net-(1F-KL)") (class "Default")
      (node (ref "1") (pin "3") (pinfunction "KL_3") (pintype "passive"))
      (node (ref "IC6") (pin "11") (pinfunction "O6_11") (pintype "open_collector"))
      (node (ref "TP3") (pin "TP") (pinfunction "PP_TP") (pintype "input"))
    )
    (net (code "9") (name "Net-(1G-KL)") (class "Default")
      (node (ref "1") (pin "4") (pinfunction "KL_4") (pintype "passive"))
      (node (ref "IC6") (pin "10") (pinfunction "O7_10") (pintype "open_collector"))
      (node (ref "TP4") (pin "TP") (pinfunction "PP_TP") (pintype "input"))
    )
    (net (code "10") (name "Net-(1H-KL)") (class "Default")
      (node (ref "1") (pin "5") (pinfunction "KL_5") (pintype "passive"))
      (node (ref "IC6") (pin "12") (pinfunction "O5_12") (pintype "open_collector"))
      (node (ref "TP5") (pin "TP") (pinfunction "PP_TP") (pintype "input"))
    )
    (net (code "11") (name "Net-(1I-KL)") (class "Default")
      (node (ref "1") (pin "6") (pinfunction "KL_6") (pintype "passive"))
      (node (ref "IC6") (pin "13") (pinfunction "O4_13") (pintype "open_collector"))
      (node (ref "TP6") (pin "TP") (pinfunction "PP_TP") (pintype "input"))
    )
    (net (code "12") (name "Net-(1J-KL)") (class "Default")
      (node (ref "1") (pin "7") (pinfunction "KL_7") (pintype "passive"))
      (node (ref "IC6") (pin "14") (pinfunction "O3_14") (pintype "open_collector"))
      (node (ref "TP7") (pin "TP") (pinfunction "PP_TP") (pintype "input"))
    )
    (net (code "13") (name "Net-(1K-KL)") (class "Default")
      (node (ref "1") (pin "8") (pinfunction "KL_8") (pintype "passive"))
      (node (ref "Q11") (pin "3") (pinfunction "D_3") (pintype "passive"))
      (node (ref "TP8") (pin "TP") (pinfunction "PP_TP") (pintype "input"))
    )
    (net (code "14") (name "Net-(1L-KL)") (class "Default")
      (node (ref "1") (pin "9") (pinfunction "KL_9") (pintype "passive"))
      (node (ref "D10") (pin "1") (pinfunction "+_1") (pintype "passive"))
      (node (ref "TP9") (pin "TP") (pinfunction "PP_TP") (pintype "input"))
      (node (ref "X1") (pin "17") (pinfunction "17_17") (pintype "passive"))
    )
    (net (code "15") (name "Net-(2B-KL)") (class "Default")
      (node (ref "2") (pin "10") (pinfunction "KL_10") (pintype "passive"))
      (node (ref "TP25") (pin "TP") (pinfunction "PP_TP") (pintype "input"))
      (node (ref "X1") (pin "15") (pinfunction "15_15") (pintype "passive"))
    )
    (net (code "16") (name "Net-(2C-KL)") (class "Default")
      (node (ref "2") (pin "11") (pinfunction "KL_11") (pintype "passive"))
      (node (ref "R23") (pin "1") (pinfunction "1_1") (pintype "passive"))
      (node (ref "R3") (pin "1") (pinfunction "1_1") (pintype "passive"))
      (node (ref "TP26") (pin "TP") (pinfunction "PP_TP") (pintype "input"))
    )
    (net (code "17") (name "Net-(2D-KL)") (class "Default")
      (node (ref "2") (pin "12") (pinfunction "KL_12") (pintype "passive"))
      (node (ref "R35") (pin "1") (pinfunction "1_1") (pintype "passive"))
      (node (ref "TP13") (pin "TP") (pinfunction "PP_TP") (pintype "input"))
    )
    (net (code "18") (name "Net-(2E-KL)") (class "Default")
      (node (ref "2") (pin "2") (pinfunction "KL_2") (pintype "passive"))
      (node (ref "D13") (pin "2") (pinfunction "-_2") (pintype "passive"))
      (node (ref "LED1") (pin "K") (pinfunction "C_K") (pintype "passive"))
      (node (ref "TP16") (pin "TP") (pinfunction "PP_TP") (pintype "input"))
      (node (ref "X1") (pin "12") (pinfunction "12_12") (pintype "passive"))
    )
    (net (code "19") (name "Net-(2F-KL)") (class "Default")
      (node (ref "2") (pin "3") (pinfunction "KL_3") (pintype "passive"))
      (node (ref "D12") (pin "2") (pinfunction "-_2") (pintype "passive"))
      (node (ref "LED2") (pin "K") (pinfunction "C_K") (pintype "passive"))
      (node (ref "TP17") (pin "TP") (pinfunction "PP_TP") (pintype "input"))
      (node (ref "X1") (pin "11") (pinfunction "11_11") (pintype "passive"))
    )
    (net (code "20") (name "Net-(2G-KL)") (class "Default")
      (node (ref "2") (pin "4") (pinfunction "KL_4") (pintype "passive"))
      (node (ref "D2") (pin "2") (pinfunction "-_2") (pintype "passive"))
      (node (ref "LED3") (pin "K") (pinfunction "C_K") (pintype "passive"))
      (node (ref "TP18") (pin "TP") (pinfunction "PP_TP") (pintype "input"))
      (node (ref "X1") (pin "10") (pinfunction "10_10") (pintype "passive"))
    )
    (net (code "21") (name "Net-(2H-KL)") (class "Default")
      (node (ref "2") (pin "5") (pinfunction "KL_5") (pintype "passive"))
      (node (ref "D1") (pin "2") (pinfunction "-_2") (pintype "passive"))
      (node (ref "LED4") (pin "K") (pinfunction "C_K") (pintype "passive"))
      (node (ref "TP19") (pin "TP") (pinfunction "PP_TP") (pintype "input"))
      (node (ref "X1") (pin "9") (pinfunction "9_9") (pintype "passive"))
    )
    (net (code "22") (name "Net-(2I-KL)") (class "Default")
      (node (ref "2") (pin "6") (pinfunction "KL_6") (pintype "passive"))
      (node (ref "TP21") (pin "TP") (pinfunction "PP_TP") (pintype "input"))
      (node (ref "U$2") (pin "2") (pinfunction "2_2") (pintype "passive"))
    )
    (net (code "23") (name "Net-(2J-KL)") (class "Default")
      (node (ref "2") (pin "7") (pinfunction "KL_7") (pintype "passive"))
      (node (ref "LED6") (pin "A") (pinfunction "A_A") (pintype "passive"))
      (node (ref "TP22") (pin "TP") (pinfunction "PP_TP") (pintype "input"))
      (node (ref "X1") (pin "8") (pinfunction "8_8") (pintype "passive"))
    )
    (net (code "24") (name "Net-(2K-KL)") (class "Default")
      (node (ref "2") (pin "8") (pinfunction "KL_8") (pintype "passive"))
      (node (ref "D14") (pin "2") (pinfunction "-_2") (pintype "passive"))
      (node (ref "LED7") (pin "K") (pinfunction "C_K") (pintype "passive"))
      (node (ref "TP23") (pin "TP") (pinfunction "PP_TP") (pintype "input"))
      (node (ref "X1") (pin "14") (pinfunction "14_14") (pintype "passive"))
    )
    (net (code "25") (name "Net-(2L-KL)") (class "Default")
      (node (ref "2") (pin "9") (pinfunction "KL_9") (pintype "passive"))
      (node (ref "D12") (pin "1") (pinfunction "+_1") (pintype "passive"))
      (node (ref "D2") (pin "1") (pinfunction "+_1") (pintype "passive"))
      (node (ref "JP2") (pin "1") (pinfunction "1_1") (pintype "passive"))
      (node (ref "JP4") (pin "2") (pinfunction "2_2") (pintype "passive"))
      (node (ref "TP24") (pin "TP") (pinfunction "PP_TP") (pintype "input"))
    )
    (net (code "26") (name "Net-(C2-Pad1)") (class "Default")
      (node (ref "C2") (pin "1") (pinfunction "1_1") (pintype "passive"))
      (node (ref "R10") (pin "1") (pinfunction "1_1") (pintype "passive"))
      (node (ref "R12") (pin "2") (pinfunction "2_2") (pintype "passive"))
    )
    (net (code "27") (name "Net-(C11-Pad1)") (class "Default")
      (node (ref "C11") (pin "1") (pinfunction "1_1") (pintype "passive"))
      (node (ref "R42") (pin "1") (pinfunction "1_1") (pintype "passive"))
      (node (ref "R43") (pin "1") (pinfunction "1_1") (pintype "passive"))
    )
    (net (code "28") (name "Net-(D1-+)") (class "Default")
      (node (ref "D1") (pin "1") (pinfunction "+_1") (pintype "passive"))
      (node (ref "R27") (pin "1") (pinfunction "1_1") (pintype "passive"))
    )
    (net (code "29") (name "Net-(D3-+)") (class "Default")
      (node (ref "D3") (pin "1") (pinfunction "+_1") (pintype "passive"))
      (node (ref "R33") (pin "1") (pinfunction "1_1") (pintype "passive"))
    )
    (net (code "30") (name "Net-(D3--)") (class "Default")
      (node (ref "C1") (pin "2") (pinfunction "2_2") (pintype "passive"))
      (node (ref "D3") (pin "2") (pinfunction "-_2") (pintype "passive"))
      (node (ref "IC5") (pin "2") (pinfunction "TR_2") (pintype "input"))
      (node (ref "IC5") (pin "6") (pinfunction "THR_6") (pintype "input"))
      (node (ref "R24") (pin "1") (pinfunction "1_1") (pintype "passive"))
      (node (ref "U$3") (pin "6") (pinfunction "D2_6") (pintype "passive"))
    )
    (net (code "31") (name "Net-(D8-+)") (class "Default")
      (node (ref "D8") (pin "1") (pinfunction "+_1") (pintype "passive"))
      (node (ref "R17") (pin "1") (pinfunction "1_1") (pintype "passive"))
    )
    (net (code "32") (name "Net-(D8--)") (class "Default")
      (node (ref "D8") (pin "2") (pinfunction "-_2") (pintype "passive"))
      (node (ref "IC7") (pin "2") (pinfunction "OUT_2") (pintype "open_collector"))
      (node (ref "Q10") (pin "1") (pinfunction "G_1") (pintype "passive"))
      (node (ref "R22") (pin "2") (pinfunction "2_2") (pintype "passive"))
      (node (ref "U$2") (pin "1") (pinfunction "1_1") (pintype "passive"))
    )
    (net (code "33") (name "Net-(D13-+)") (class "Default")
      (node (ref "D13") (pin "1") (pinfunction "+_1") (pintype "passive"))
      (node (ref "JP2") (pin "2") (pinfunction "2_2") (pintype "passive"))
    )
    (net (code "34") (name "Net-(D14-+)") (class "Default")
      (node (ref "D14") (pin "1") (pinfunction "+_1") (pintype "passive"))
      (node (ref "JP4") (pin "1") (pinfunction "1_1") (pintype "passive"))
    )
    (net (code "35") (name "Net-(D15--)") (class "Default")
      (node (ref "D15") (pin "2") (pinfunction "-_2") (pintype "passive"))
      (node (ref "Q1") (pin "2") (pinfunction "C_2") (pintype "passive"))
      (node (ref "Q3") (pin "2") (pinfunction "C_2") (pintype "passive"))
      (node (ref "START") (pin "TP") (pinfunction "PP_TP") (pintype "input"))
      (node (ref "X1") (pin "5") (pinfunction "5_5") (pintype "passive"))
    )
    (net (code "36") (name "Net-(IC3A-A)") (class "Default")
      (node (ref "IC3") (pin "10") (pinfunction "A_10") (pintype "input"))
      (node (ref "R31") (pin "1") (pinfunction "1_1") (pintype "passive"))
      (node (ref "U$3") (pin "1") (pinfunction "D1_1") (pintype "passive"))
      (node (ref "X1") (pin "4") (pinfunction "4_4") (pintype "passive"))
      (node (ref "X3") (pin "2") (pinfunction "S_2") (pintype "passive"))
    )
    (net (code "37") (name "Net-(IC3A-B)") (class "Default")
      (node (ref "IC3") (pin "13") (pinfunction "B_13") (pintype "input"))
      (node (ref "R30") (pin "1") (pinfunction "1_1") (pintype "passive"))
      (node (ref "U$3") (pin "4") (pinfunction "D4_4") (pintype "passive"))
      (node (ref "X1") (pin "3") (pinfunction "3_3") (pintype "passive"))
      (node (ref "X3") (pin "3") (pinfunction "S_3") (pintype "passive"))
    )
    (net (code "38") (name "Net-(IC3A-C)") (class "Default")
      (node (ref "IC3") (pin "12") (pinfunction "C_12") (pintype "input"))
      (node (ref "R29") (pin "1") (pinfunction "1_1") (pintype "passive"))
      (node (ref "U$3") (pin "3") (pinfunction "D3_3") (pintype "passive"))
      (node (ref "X1") (pin "2") (pinfunction "2_2") (pintype "passive"))
      (node (ref "X3") (pin "4") (pinfunction "S_4") (pintype "passive"))
    )
    (net (code "39") (name "Net-(IC3A-Q0)") (class "Default")
      (node (ref "IC3") (pin "3") (pinfunction "Q0_3") (pintype "output"))
      (node (ref "IC6") (pin "1") (pinfunction "I1_1") (pintype "input"))
      (node (ref "IC6") (pin "2") (pinfunction "I2_2") (pintype "input"))
      (node (ref "Q11") (pin "1") (pinfunction "G_1") (pintype "passive"))
    )
    (net (code "40") (name "Net-(IC3A-Q1)") (class "Default")
      (node (ref "IC3") (pin "14") (pinfunction "Q1_14") (pintype "output"))
      (node (ref "IC6") (pin "6") (pinfunction "I6_6") (pintype "input"))
    )
    (net (code "41") (name "Net-(IC3A-Q2)") (class "Default")
      (node (ref "IC3") (pin "2") (pinfunction "Q2_2") (pintype "output"))
      (node (ref "IC6") (pin "7") (pinfunction "I7_7") (pintype "input"))
    )
    (net (code "42") (name "Net-(IC3A-Q3)") (class "Default")
      (node (ref "IC3") (pin "15") (pinfunction "Q3_15") (pintype "output"))
      (node (ref "IC6") (pin "5") (pinfunction "I5_5") (pintype "input"))
    )
    (net (code "43") (name "Net-(IC3A-Q4)") (class "Default")
      (node (ref "IC3") (pin "1") (pinfunction "Q4_1") (pintype "output"))
      (node (ref "IC6") (pin "4") (pinfunction "I4_4") (pintype "input"))
    )
    (net (code "44") (name "Net-(IC3A-Q5)") (class "Default")
      (node (ref "IC3") (pin "6") (pinfunction "Q5_6") (pintype "output"))
      (node (ref "IC6") (pin "3") (pinfunction "I3_3") (pintype "input"))
    )
    (net (code "45") (name "Net-(IC4-ADJ)") (class "Default")
      (node (ref "IC4") (pin "1") (pinfunction "ADJ_1") (pintype "input"))
      (node (ref "R18") (pin "1") (pinfunction "1_1") (pintype "passive"))
      (node (ref "R5") (pin "2") (pinfunction "2_2") (pintype "passive"))
      (node (ref "X1") (pin "7") (pinfunction "7_7") (pintype "passive"))
    )
    (net (code "46") (name "Net-(IC4-VI)") (class "Default")
      (node (ref "IC4") (pin "3") (pinfunction "VI_3") (pintype "input"))
      (node (ref "Q2") (pin "2") (pinfunction "C_2") (pintype "passive"))
      (node (ref "Q4") (pin "2") (pinfunction "C_2") (pintype "passive"))
    )
    (net (code "47") (name "Net-(IC4-VO)") (class "Default")
      (node (ref "IC4") (pin "2") (pinfunction "VO_2") (pintype "passive"))
      (node (ref "R18") (pin "2") (pinfunction "2_2") (pintype "passive"))
    )
    (net (code "48") (name "Net-(IC5-CV)") (class "Default")
      (node (ref "IC5") (pin "5") (pinfunction "CV_5") (pintype "input"))
      (node (ref "R26") (pin "2") (pinfunction "2_2") (pintype "passive"))
    )
    (net (code "49") (name "Net-(IC5-Q)") (class "Default")
      (node (ref "IC5") (pin "3") (pinfunction "Q_3") (pintype "output"))
      (node (ref "IC8") (pin "12") (pinfunction "A_12") (pintype "input"))
      (node (ref "R26") (pin "1") (pinfunction "1_1") (pintype "passive"))
    )
    (net (code "50") (name "Net-(IC6-O1)") (class "Default")
      (node (ref "IC6") (pin "16") (pinfunction "O1_16") (pintype "open_collector"))
      (node (ref "Q9") (pin "2") (pinfunction "C_2") (pintype "passive"))
      (node (ref "R3") (pin "2") (pinfunction "2_2") (pintype "passive"))
      (node (ref "T3") (pin "C") (pinfunction "C_C") (pintype "passive"))
      (node (ref "X1") (pin "21") (pinfunction "21_21") (pintype "passive"))
    )
    (net (code "51") (name "Net-(IC6-O2)") (class "Default")
      (node (ref "IC6") (pin "15") (pinfunction "O2_15") (pintype "open_collector"))
      (node (ref "R13") (pin "1") (pinfunction "1_1") (pintype "passive"))
    )
    (net (code "52") (name "Net-(IC7A-+IN)") (class "Default")
      (node (ref "IC7") (pin "5") (pinfunction "+IN_5") (pintype "input"))
      (node (ref "R15") (pin "1") (pinfunction "1_1") (pintype "passive"))
      (node (ref "R16") (pin "2") (pinfunction "2_2") (pintype "passive"))
      (node (ref "R17") (pin "2") (pinfunction "2_2") (pintype "passive"))
    )
    (net (code "53") (name "Net-(IC7A--IN)") (class "Default")
      (node (ref "C3") (pin "1") (pinfunction "1_1") (pintype "passive"))
      (node (ref "IC7") (pin "4") (pinfunction "-IN_4") (pintype "input"))
      (node (ref "R12") (pin "1") (pinfunction "1_1") (pintype "passive"))
    )
    (net (code "54") (name "Net-(IC7B-+IN)") (class "Default")
      (node (ref "IC7") (pin "7") (pinfunction "+IN_7") (pintype "input"))
      (node (ref "R25") (pin "1") (pinfunction "1_1") (pintype "passive"))
      (node (ref "R6") (pin "1") (pinfunction "1_1") (pintype "passive"))
    )
    (net (code "55") (name "Net-(IC7B--IN)") (class "Default")
      (node (ref "IC7") (pin "6") (pinfunction "-IN_6") (pintype "input"))
      (node (ref "IC7") (pin "8") (pinfunction "-IN_8") (pintype "input"))
      (node (ref "R5") (pin "1") (pinfunction "1_1") (pintype "passive"))
    )
    (net (code "56") (name "Net-(IC7B-OUT)") (class "Default")
      (node (ref "IC7") (pin "1") (pinfunction "OUT_1") (pintype "open_collector"))
      (node (ref "R10") (pin "2") (pinfunction "2_2") (pintype "passive"))
      (node (ref "R19") (pin "2") (pinfunction "2_2") (pintype "passive"))
    )
    (net (code "57") (name "Net-(IC7C-+IN)") (class "Default")
      (node (ref "C5") (pin "1") (pinfunction "1_1") (pintype "passive"))
      (node (ref "IC7") (pin "9") (pinfunction "+IN_9") (pintype "input"))
      (node (ref "R25") (pin "2") (pinfunction "2_2") (pintype "passive"))
      (node (ref "R8") (pin "2") (pinfunction "2_2") (pintype "passive"))
    )
    (net (code "58") (name "Net-(IC7C-OUT)") (class "Default")
      (node (ref "C9") (pin "2") (pinfunction "2_2") (pintype "passive"))
      (node (ref "IC7") (pin "14") (pinfunction "OUT_14") (pintype "open_collector"))
      (node (ref "R9") (pin "2") (pinfunction "2_2") (pintype "passive"))
    )
    (net (code "59") (name "Net-(IC8B-B)") (class "Default")
      (node (ref "IC8") (pin "11") (pinfunction "B_11") (pintype "input"))
      (node (ref "IC8") (pin "9") (pinfunction "~{Q}_9") (pintype "output"))
      (node (ref "R35") (pin "2") (pinfunction "2_2") (pintype "passive"))
    )
    (net (code "60") (name "Net-(IC8B-T2)") (class "Default")
      (node (ref "C10") (pin "1") (pinfunction "1_1") (pintype "passive"))
      (node (ref "IC8") (pin "14") (pinfunction "T2_14") (pintype "input"))
      (node (ref "R34") (pin "1") (pinfunction "1_1") (pintype "passive"))
    )
    (net (code "61") (name "Net-(IC10A-+IN)") (class "Default")
      (node (ref "C8") (pin "1") (pinfunction "1_1") (pintype "passive"))
      (node (ref "IC10") (pin "3") (pinfunction "+IN_3") (pintype "input"))
      (node (ref "R1") (pin "1") (pinfunction "1_1") (pintype "passive"))
    )
    (net (code "62") (name "Net-(IC10A--IN)") (class "Default")
      (node (ref "IC10") (pin "2") (pinfunction "-IN_2") (pintype "input"))
      (node (ref "R2") (pin "2") (pinfunction "2_2") (pintype "passive"))
    )
    (net (code "63") (name "Net-(IC10A-OUT)") (class "Default")
      (node (ref "IC10") (pin "1") (pinfunction "OUT_1") (pintype "output"))
      (node (ref "R42") (pin "2") (pinfunction "2_2") (pintype "passive"))
    )
    (net (code "64") (name "Net-(IC10B-+IN)") (class "Default")
      (node (ref "IC10") (pin "5") (pinfunction "+IN_5") (pintype "input"))
      (node (ref "R43") (pin "2") (pinfunction "2_2") (pintype "passive"))
      (node (ref "R44") (pin "2") (pinfunction "2_2") (pintype "passive"))
    )
    (net (code "65") (name "Net-(IC10B--IN)") (class "Default")
      (node (ref "IC10") (pin "6") (pinfunction "-IN_6") (pintype "input"))
      (node (ref "R45") (pin "1") (pinfunction "1_1") (pintype "passive"))
      (node (ref "R46") (pin "2") (pinfunction "2_2") (pintype "passive"))
    )
    (net (code "66") (name "Net-(IC10B-OUT)") (class "Default")
      (node (ref "IC10") (pin "7") (pinfunction "OUT_7") (pintype "output"))
      (node (ref "R32") (pin "1") (pinfunction "1_1") (pintype "passive"))
      (node (ref "R44") (pin "1") (pinfunction "1_1") (pintype "passive"))
    )
    (net (code "67") (name "Net-(JP1-Pad2)") (class "Default")
      (node (ref "JP1") (pin "2") (pinfunction "2_2") (pintype "passive"))
      (node (ref "R36") (pin "2") (pinfunction "2_2") (pintype "passive"))
      (node (ref "R37") (pin "2") (pinfunction "2_2") (pintype "passive"))
    )
    (net (code "68") (name "Net-(JP3-Pad1)") (class "Default")
      (node (ref "JP3") (pin "1") (pinfunction "1_1") (pintype "passive"))
      (node (ref "R23") (pin "2") (pinfunction "2_2") (pintype "passive"))
    )
    (net (code "69") (name "Net-(LED1-PadA)") (class "Default")
      (node (ref "LED1") (pin "A") (pinfunction "A_A") (pintype "passive"))
      (node (ref "LED2") (pin "A") (pinfunction "A_A") (pintype "passive"))
      (node (ref "LED3") (pin "A") (pinfunction "A_A") (pintype "passive"))
      (node (ref "LED4") (pin "A") (pinfunction "A_A") (pintype "passive"))
      (node (ref "LED7") (pin "A") (pinfunction "A_A") (pintype "passive"))
      (node (ref "R11") (pin "1") (pinfunction "1_1") (pintype "passive"))
    )
    (net (code "70") (name "Net-(LED6-C)") (class "Default")
      (node (ref "LED6") (pin "K") (pinfunction "C_K") (pintype "passive"))
      (node (ref "R4") (pin "1") (pinfunction "1_1") (pintype "passive"))
    )
    (net (code "71") (name "Net-(Q1-B)") (class "Default")
      (node (ref "Q1") (pin "1") (pinfunction "B_1") (pintype "passive"))
      (node (ref "Q3") (pin "1") (pinfunction "B_1") (pintype "passive"))
      (node (ref "R13") (pin "2") (pinfunction "2_2") (pintype "passive"))
    )
    (net (code "72") (name "Net-(Q2-B)") (class "Default")
      (node (ref "Q2") (pin "1") (pinfunction "B_1") (pintype "passive"))
      (node (ref "Q4") (pin "1") (pinfunction "B_1") (pintype "passive"))
      (node (ref "R9") (pin "1") (pinfunction "1_1") (pintype "passive"))
    )
    (net (code "73") (name "Net-(Q5-B)") (class "Default")
      (node (ref "Q5") (pin "1") (pinfunction "B_1") (pintype "passive"))
      (node (ref "Q6") (pin "1") (pinfunction "B_1") (pintype "passive"))
      (node (ref "Q6") (pin "2") (pinfunction "C_2") (pintype "passive"))
      (node (ref "Q7") (pin "1") (pinfunction "B_1") (pintype "passive"))
      (node (ref "Q7") (pin "2") (pinfunction "C_2") (pintype "passive"))
      (node (ref "Q8") (pin "1") (pinfunction "B_1") (pintype "passive"))
      (node (ref "R38") (pin "1") (pinfunction "1_1") (pintype "passive"))
      (node (ref "R39") (pin "1") (pinfunction "1_1") (pintype "passive"))
      (node (ref "T1") (pin "2") (pinfunction "B_2") (pintype "passive"))
      (node (ref "T1") (pin "4") (pinfunction "B_4") (pintype "passive"))
      (node (ref "T1") (pin "6") (pinfunction "C1_6") (pintype "passive"))
      (node (ref "X2") (pin "2") (pinfunction "S_2") (pintype "passive"))
    )
    (net (code "74") (name "Net-(Q5-E)") (class "Default")
      (node (ref "Q5") (pin "3") (pinfunction "E_3") (pintype "passive"))
      (node (ref "Q8") (pin "3") (pinfunction "E_3") (pintype "passive"))
      (node (ref "R21") (pin "2") (pinfunction "2_2") (pintype "passive"))
      (node (ref "T1") (pin "1") (pinfunction "E_1") (pintype "passive"))
    )
    (net (code "75") (name "Net-(Q6-E)") (class "Default")
      (node (ref "Q6") (pin "3") (pinfunction "E_3") (pintype "passive"))
      (node (ref "Q7") (pin "3") (pinfunction "E_3") (pintype "passive"))
      (node (ref "R20") (pin "2") (pinfunction "2_2") (pintype "passive"))
      (node (ref "T1") (pin "3") (pinfunction "E_3") (pintype "passive"))
    )
    (net (code "76") (name "Net-(Q9-B)") (class "Default")
      (node (ref "Q9") (pin "1") (pinfunction "B_1") (pintype "passive"))
      (node (ref "R32") (pin "2") (pinfunction "2_2") (pintype "passive"))
      (node (ref "T3") (pin "B") (pinfunction "B_B") (pintype "passive"))
    )
    (net (code "77") (name "Net-(Q10-D)") (class "Default")
      (node (ref "Q10") (pin "3") (pinfunction "D_3") (pintype "passive"))
      (node (ref "R7") (pin "2") (pinfunction "2_2") (pintype "passive"))
    )
    (net (code "78") (name "Net-(R1-Pad2)") (class "Default")
      (node (ref "R1") (pin "2") (pinfunction "2_2") (pintype "passive"))
      (node (ref "X1") (pin "22") (pinfunction "22_22") (pintype "passive"))
    )
    (net (code "79") (name "Net-(R14-Pad1)") (class "Default")
      (node (ref "R14") (pin "1") (pinfunction "1_1") (pintype "passive"))
      (node (ref "R7") (pin "1") (pinfunction "1_1") (pintype "passive"))
      (node (ref "U$2") (pin "3") (pinfunction "3_3") (pintype "passive"))
    )
    (net (code "80") (name "Net-(R27-Pad2)") (class "Default")
      (node (ref "R27") (pin "2") (pinfunction "2_2") (pintype "passive"))
      (node (ref "R28") (pin "1") (pinfunction "1_1") (pintype "passive"))
    )
    (net (code "81") (name "Net-(R33-Pad2)") (class "Default")
      (node (ref "R33") (pin "2") (pinfunction "2_2") (pintype "passive"))
      (node (ref "X1") (pin "16") (pinfunction "16_16") (pintype "passive"))
    )
    (net (code "82") (name "Net-(TACHO_BEL-PP)") (class "Default")
      (node (ref "TACHO_BEL") (pin "TP") (pinfunction "PP_TP") (pintype "input"))
      (node (ref "X1") (pin "24") (pinfunction "24_24") (pintype "passive"))
    )
    (net (code "83") (name "VCC") (class "Default")
      (node (ref "6V") (pin "TP") (pinfunction "PP_TP") (pintype "input"))
      (node (ref "C4") (pin "1") (pinfunction "1_1") (pintype "passive"))
      (node (ref "IC1") (pin "OUT") (pinfunction "OUT_OUT") (pintype "passive"))
      (node (ref "IC10") (pin "8") (pinfunction "V+_8") (pintype "power_in"))
      (node (ref "IC2") (pin "1") (pinfunction "OUT_1") (pintype "passive"))
      (node (ref "IC7") (pin "3") (pinfunction "V+_3") (pintype "power_in"))
      (node (ref "R11") (pin "2") (pinfunction "2_2") (pintype "passive"))
      (node (ref "R15") (pin "2") (pinfunction "2_2") (pintype "passive"))
      (node (ref "R19") (pin "1") (pinfunction "1_1") (pintype "passive"))
      (node (ref "R45") (pin "2") (pinfunction "2_2") (pintype "passive"))
      (node (ref "R6") (pin "2") (pinfunction "2_2") (pintype "passive"))
    )
    (net (code "84") (name "unconnected-(IC3A-Q6-Pad7)") (class "Default")
      (node (ref "IC3") (pin "7") (pinfunction "Q6_7") (pintype "output"))
    )
    (net (code "85") (name "unconnected-(IC3A-Q7-Pad4)") (class "Default")
      (node (ref "IC3") (pin "4") (pinfunction "Q7_4") (pintype "output"))
    )
    (net (code "86") (name "unconnected-(IC3A-Q8-Pad9)") (class "Default")
      (node (ref "IC3") (pin "9") (pinfunction "Q8_9") (pintype "output"))
    )
    (net (code "87") (name "unconnected-(IC3A-Q9-Pad5)") (class "Default")
      (node (ref "IC3") (pin "5") (pinfunction "Q9_5") (pintype "output"))
    )
    (net (code "88") (name "unconnected-(IC5-DIS-Pad7)") (class "Default")
      (node (ref "IC5") (pin "7") (pinfunction "DIS_7") (pintype "input"))
    )
    (net (code "89") (name "unconnected-(IC6-CD+-Pad9)") (class "Default")
      (node (ref "IC6") (pin "9") (pinfunction "CD+_9") (pintype "passive"))
    )
    (net (code "90") (name "unconnected-(IC7D-OUT-Pad13)") (class "Default")
      (node (ref "IC7") (pin "13") (pinfunction "OUT_13") (pintype "open_collector"))
    )
    (net (code "91") (name "unconnected-(IC8A-Q-Pad6)") (class "Default")
      (node (ref "IC8") (pin "6") (pinfunction "Q_6") (pintype "output"))
    )
    (net (code "92") (name "unconnected-(IC8A-T2-Pad2)") (class "Default")
      (node (ref "IC8") (pin "2") (pinfunction "T2_2") (pintype "input"))
    )
    (net (code "93") (name "unconnected-(IC8A-~{Q}-Pad7)") (class "Default")
      (node (ref "IC8") (pin "7") (pinfunction "~{Q}_7") (pintype "output"))
    )
    (net (code "94") (name "unconnected-(IC8B-Q-Pad10)") (class "Default")
      (node (ref "IC8") (pin "10") (pinfunction "Q_10") (pintype "output"))
    )
    (net (code "95") (name "unconnected-(Q3-C{slash}-Pad4)") (class "Default")
      (node (ref "Q3") (pin "4") (pinfunction "C/_4") (pintype "passive"))
    )
    (net (code "96") (name "unconnected-(Q4-C{slash}-Pad4)") (class "Default")
      (node (ref "Q4") (pin "4") (pinfunction "C/_4") (pintype "passive"))
    )
    (net (code "97") (name "unconnected-(Q5-C{slash}-Pad4)") (class "Default")
      (node (ref "Q5") (pin "4") (pinfunction "C/_4") (pintype "passive"))
    )
    (net (code "98") (name "unconnected-(Q6-C{slash}-Pad4)") (class "Default")
      (node (ref "Q6") (pin "4") (pinfunction "C/_4") (pintype "passive"))
    )
    (net (code "99") (name "unconnected-(T1A-C-Pad5)") (class "Default")
      (node (ref "T1") (pin "5") (pinfunction "C_5") (pintype "passive"))
    )
    (net (code "100") (name "unconnected-(T1B-C-Pad7)") (class "Default")
      (node (ref "T1") (pin "7") (pinfunction "C_7") (pintype "passive"))
    )
    (net (code "101") (name "unconnected-(X1-Pad20)") (class "Default")
      (node (ref "X1") (pin "20") (pinfunction "20_20") (pintype "passive"))
    )
  )
)
